# MCU.net
KiCad netlist of a schematic drawn in Altium Designer
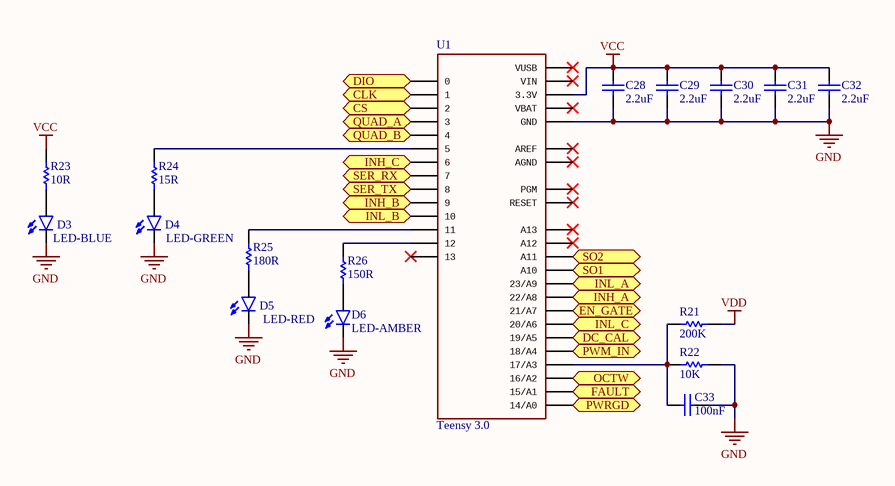
[diagram p0: MCU.SchDoc]

(export (version "E")
  (design (tool "Eeschema 10.0.6"))
  (components
    (comp (ref "C28")
      (value "2.2uF")
      (footprint "CAPC0603(1608)55_N")
      (description "CAP 2.2uF 16V Â±10% 0603 (1608 Metric) Thickness 0.55mm SMD")
      (fields (field (name "TOLERANCE") "Â±10%"))
      (libsource (lib "Altium Content Vault") (part "CMP-1035-02762-1"))
    )
    (comp (ref "C29")
      (value "2.2uF")
      (footprint "CAPC0603(1608)55_N")
      (description "CAP 2.2uF 16V Â±10% 0603 (1608 Metric) Thickness 0.55mm SMD")
      (fields (field (name "TOLERANCE") "Â±10%"))
      (libsource (lib "Altium Content Vault") (part "CMP-1035-02762-1"))
    )
    (comp (ref "C30")
      (value "2.2uF")
      (footprint "CAPC0603(1608)55_N")
      (description "CAP 2.2uF 16V Â±10% 0603 (1608 Metric) Thickness 0.55mm SMD")
      (fields (field (name "TOLERANCE") "Â±10%"))
      (libsource (lib "Altium Content Vault") (part "CMP-1035-02762-1"))
    )
    (comp (ref "C31")
      (value "2.2uF")
      (footprint "CAPC0603(1608)55_N")
      (description "CAP 2.2uF 16V Â±10% 0603 (1608 Metric) Thickness 0.55mm SMD")
      (fields (field (name "TOLERANCE") "Â±10%"))
      (libsource (lib "Altium Content Vault") (part "CMP-1035-02762-1"))
    )
    (comp (ref "C32")
      (value "2.2uF")
      (footprint "CAPC0603(1608)55_N")
      (description "CAP 2.2uF 16V Â±10% 0603 (1608 Metric) Thickness 0.55mm SMD")
      (fields (field (name "TOLERANCE") "Â±10%"))
      (libsource (lib "Altium Content Vault") (part "CMP-1035-02762-1"))
    )
    (comp (ref "C33")
      (value "100nF")
      (footprint "CAPC0603(1608)100_L")
      (description "CAP 100nF 50V Â±5% 0603 (1608 Metric) Thickness 1mm SMD")
      (fields (field (name "TOLERANCE") "Â±5%"))
      (libsource (lib "Altium Content Vault") (part "CAP"))
    )
    (comp (ref "D3")
      (value "LED-BLUE")
      (footprint "LED-1206")
      (libsource (lib "Components") (part "LED-BLUE1206"))
    )
    (comp (ref "D4")
      (value "LED-GREEN")
      (footprint "LED-1206")
      (libsource (lib "Components") (part "LED-GREEN1206"))
    )
    (comp (ref "D5")
      (value "LED-RED")
      (footprint "LED-1206")
      (libsource (lib "Components") (part "LED-RED1206"))
    )
    (comp (ref "D6")
      (value "LED-AMBER")
      (footprint "LED-1206")
      (libsource (lib "Components") (part "LED-AMBER1206"))
    )
    (comp (ref "R21")
      (value "200K")
      (footprint "RESC0603(1608)_L")
      (description "200K 0.1W 5% 0603 (1608 Metric)  SMD")
      (fields (field (name "POWER") "0.1 W") (field (name "TOLERANCE") "5 %"))
      (libsource (lib "Altium Content Vault") (part "RES"))
    )
    (comp (ref "R22")
      (value "10K")
      (footprint "RESC0603(1608)_M")
      (description "10K 0.1W 5% 0603 (1608 Metric)  SMD")
      (fields (field (name "TOLERANCE") "5 %") (field (name "POWER") "0.1 W"))
      (libsource (lib "Altium Content Vault") (part "RES"))
    )
    (comp (ref "R23")
      (value "10R")
      (footprint "RESC0603(1608)_N")
      (description "10R 0.1W 5% 0603 (1608 Metric)  SMD")
      (fields (field (name "TOLERANCE") "5 %") (field (name "POWER") "0.1 W"))
      (libsource (lib "Altium Content Vault") (part "CMP-1012-00026-1"))
    )
    (comp (ref "R24")
      (value "15R")
      (footprint "RESC0603(1608)_N")
      (description "15R 0.1W 5% 0603 (1608 Metric)  SMD")
      (fields (field (name "TOLERANCE") "5 %") (field (name "POWER") "0.1 W"))
      (libsource (lib "Altium Content Vault") (part "CMP-1012-00030-1"))
    )
    (comp (ref "R25")
      (value "180R")
      (footprint "RESC0603(1608)_N")
      (description "180R 0.1W 5% 0603 (1608 Metric)  SMD")
      (fields (field (name "POWER") "0.1 W") (field (name "TOLERANCE") "5 %"))
      (libsource (lib "Altium Content Vault") (part "CMP-1012-00056-1"))
    )
    (comp (ref "R26")
      (value "150R")
      (footprint "RESC0603(1608)_N")
      (description "150R 0.1W 5% 0603 (1608 Metric)  SMD")
      (fields (field (name "POWER") "0.1 W") (field (name "TOLERANCE") "5 %"))
      (libsource (lib "Altium Content Vault") (part "CMP-1012-00054-1"))
    )
    (comp (ref "U1")
      (value "Teensy 3.0")
      (footprint "TEENSY_3.0_ALLANALOG")
      (libsource (lib "Teensy3.0") (part "TEENSY_3.0_ALLANALOGPINS"))
    )
  )
  (nets
    (net (code "1") (name "/CLK") (class "Default")
      (node (ref "U1") (pin "1") (pinfunction "1_1") (pintype "passive"))
    )
    (net (code "2") (name "/CS") (class "Default")
      (node (ref "U1") (pin "2") (pinfunction "2_2") (pintype "passive"))
    )
    (net (code "3") (name "/DC_CAL") (class "Default")
      (node (ref "U1") (pin "19/A5") (pinfunction "19/A5_19/A5") (pintype "passive"))
    )
    (net (code "4") (name "/DIO") (class "Default")
      (node (ref "U1") (pin "0") (pinfunction "0_0") (pintype "passive"))
    )
    (net (code "5") (name "/EN_GATE") (class "Default")
      (node (ref "U1") (pin "21/A7") (pinfunction "21/A7_21/A7") (pintype "passive"))
    )
    (net (code "6") (name "/FAULT") (class "Default")
      (node (ref "U1") (pin "15/A1") (pinfunction "15/A1_15/A1") (pintype "passive"))
    )
    (net (code "7") (name "/INH_A") (class "Default")
      (node (ref "U1") (pin "22/A8") (pinfunction "22/A8_22/A8") (pintype "passive"))
    )
    (net (code "8") (name "/INH_B") (class "Default")
      (node (ref "U1") (pin "9") (pinfunction "9_9") (pintype "passive"))
    )
    (net (code "9") (name "/INH_C") (class "Default")
      (node (ref "U1") (pin "6") (pinfunction "6_6") (pintype "passive"))
    )
    (net (code "10") (name "/INL_A") (class "Default")
      (node (ref "U1") (pin "23/A9") (pinfunction "23/A9_23/A9") (pintype "passive"))
    )
    (net (code "11") (name "/INL_B") (class "Default")
      (node (ref "U1") (pin "10") (pinfunction "10_10") (pintype "passive"))
    )
    (net (code "12") (name "/INL_C") (class "Default")
      (node (ref "U1") (pin "20/A6") (pinfunction "20/A6_20/A6") (pintype "passive"))
    )
    (net (code "13") (name "/OCTW") (class "Default")
      (node (ref "U1") (pin "16/A2") (pinfunction "16/A2_16/A2") (pintype "passive"))
    )
    (net (code "14") (name "/PWM_IN") (class "Default")
      (node (ref "U1") (pin "18/A4") (pinfunction "18/A4_18/A4") (pintype "passive"))
    )
    (net (code "15") (name "/PWRGD") (class "Default")
      (node (ref "U1") (pin "14/A0") (pinfunction "14/A0_14/A0") (pintype "passive"))
    )
    (net (code "16") (name "/QUAD_A") (class "Default")
      (node (ref "U1") (pin "3") (pinfunction "3_3") (pintype "passive"))
    )
    (net (code "17") (name "/QUAD_B") (class "Default")
      (node (ref "U1") (pin "4") (pinfunction "4_4") (pintype "passive"))
    )
    (net (code "18") (name "/SER_RX") (class "Default")
      (node (ref "U1") (pin "7") (pinfunction "7_7") (pintype "passive"))
    )
    (net (code "19") (name "/SER_TX") (class "Default")
      (node (ref "U1") (pin "8") (pinfunction "8_8") (pintype "passive"))
    )
    (net (code "20") (name "/SO1") (class "Default")
      (node (ref "U1") (pin "A10") (pinfunction "A10_A10") (pintype "passive"))
    )
    (net (code "21") (name "/SO2") (class "Default")
      (node (ref "U1") (pin "A11") (pinfunction "A11_A11") (pintype "passive"))
    )
    (net (code "22") (name "GND") (class "Default")
      (node (ref "C28") (pin "1") (pinfunction "1_1") (pintype "passive"))
      (node (ref "C29") (pin "1") (pinfunction "1_1") (pintype "passive"))
      (node (ref "C30") (pin "1") (pinfunction "1_1") (pintype "passive"))
      (node (ref "C31") (pin "1") (pinfunction "1_1") (pintype "passive"))
      (node (ref "C32") (pin "1") (pinfunction "1_1") (pintype "passive"))
      (node (ref "C33") (pin "2") (pinfunction "2_2") (pintype "passive"))
      (node (ref "D3") (pin "C") (pinfunction "C_C") (pintype "passive"))
      (node (ref "D4") (pin "C") (pinfunction "C_C") (pintype "passive"))
      (node (ref "D5") (pin "C") (pinfunction "C_C") (pintype "passive"))
      (node (ref "D6") (pin "C") (pinfunction "C_C") (pintype "passive"))
      (node (ref "R22") (pin "2") (pinfunction "2_2") (pintype "passive"))
      (node (ref "U1") (pin "GND_GND1_GND2") (pinfunction "GND_GND_GND1_GND2") (pintype "power_in"))
    )
    (net (code "23") (name "Net-(C33-Pad1)") (class "Default")
      (node (ref "C33") (pin "1") (pinfunction "1_1") (pintype "passive"))
      (node (ref "R21") (pin "1") (pinfunction "1_1") (pintype "passive"))
      (node (ref "R22") (pin "1") (pinfunction "1_1") (pintype "passive"))
      (node (ref "U1") (pin "17/A3") (pinfunction "17/A3_17/A3") (pintype "passive"))
    )
    (net (code "24") (name "Net-(D3-PadA)") (class "Default")
      (node (ref "D3") (pin "A") (pinfunction "A_A") (pintype "passive"))
      (node (ref "R23") (pin "1") (pinfunction "1_1") (pintype "passive"))
    )
    (net (code "25") (name "Net-(D4-PadA)") (class "Default")
      (node (ref "D4") (pin "A") (pinfunction "A_A") (pintype "passive"))
      (node (ref "R24") (pin "1") (pinfunction "1_1") (pintype "passive"))
    )
    (net (code "26") (name "Net-(D5-PadA)") (class "Default")
      (node (ref "D5") (pin "A") (pinfunction "A_A") (pintype "passive"))
      (node (ref "R25") (pin "1") (pinfunction "1_1") (pintype "passive"))
    )
    (net (code "27") (name "Net-(D6-PadA)") (class "Default")
      (node (ref "D6") (pin "A") (pinfunction "A_A") (pintype "passive"))
      (node (ref "R26") (pin "1") (pinfunction "1_1") (pintype "passive"))
    )
    (net (code "28") (name "Net-(R24-Pad2)") (class "Default")
      (node (ref "R24") (pin "2") (pinfunction "2_2") (pintype "passive"))
      (node (ref "U1") (pin "5") (pinfunction "5_5") (pintype "passive"))
    )
    (net (code "29") (name "Net-(R25-Pad2)") (class "Default")
      (node (ref "R25") (pin "2") (pinfunction "2_2") (pintype "passive"))
      (node (ref "U1") (pin "11") (pinfunction "11_11") (pintype "passive"))
    )
    (net (code "30") (name "Net-(R26-Pad2)") (class "Default")
      (node (ref "R26") (pin "2") (pinfunction "2_2") (pintype "passive"))
      (node (ref "U1") (pin "12") (pinfunction "12_12") (pintype "passive"))
    )
    (net (code "31") (name "VCC") (class "Default")
      (node (ref "C28") (pin "2") (pinfunction "2_2") (pintype "passive"))
      (node (ref "C29") (pin "2") (pinfunction "2_2") (pintype "passive"))
      (node (ref "C30") (pin "2") (pinfunction "2_2") (pintype "passive"))
      (node (ref "C31") (pin "2") (pinfunction "2_2") (pintype "passive"))
      (node (ref "C32") (pin "2") (pinfunction "2_2") (pintype "passive"))
      (node (ref "R23") (pin "2") (pinfunction "2_2") (pintype "passive"))
      (node (ref "U1") (pin "3.3V_3.3V1_3.3V2") (pinfunction "3.3V_3.3V_3.3V1_3.3V2") (pintype "power_in"))
    )
    (net (code "32") (name "VDD") (class "Default")
      (node (ref "R21") (pin "2") (pinfunction "2_2") (pintype "passive"))
    )
    (net (code "33") (name "unconnected-(U1-Pad13)") (class "Default")
      (node (ref "U1") (pin "13") (pinfunction "13_13") (pintype "passive+no_connect"))
    )
    (net (code "34") (name "unconnected-(U1-PadA12)") (class "Default")
      (node (ref "U1") (pin "A12") (pinfunction "A12_A12") (pintype "passive+no_connect"))
    )
    (net (code "35") (name "unconnected-(U1-PadA13)") (class "Default")
      (node (ref "U1") (pin "A13") (pinfunction "A13_A13") (pintype "passive+no_connect"))
    )
    (net (code "36") (name "unconnected-(U1-PadAGND)") (class "Default")
      (node (ref "U1") (pin "AGND") (pinfunction "AGND_AGND") (pintype "power_in+no_connect"))
    )
    (net (code "37") (name "unconnected-(U1-PadAREF)") (class "Default")
      (node (ref "U1") (pin "AREF") (pinfunction "AREF_AREF") (pintype "power_in+no_connect"))
    )
    (net (code "38") (name "unconnected-(U1-PadPGM)") (class "Default")
      (node (ref "U1") (pin "PGM") (pinfunction "PGM_PGM") (pintype "power_in+no_connect"))
    )
    (net (code "39") (name "unconnected-(U1-PadVBAT)") (class "Default")
      (node (ref "U1") (pin "VBAT") (pinfunction "VBAT_VBAT") (pintype "power_in+no_connect"))
    )
    (net (code "40") (name "unconnected-(U1-PadVIN)") (class "Default")
      (node (ref "U1") (pin "VIN") (pinfunction "VIN_VIN") (pintype "power_in+no_connect"))
    )
    (net (code "41") (name "unconnected-(U1-PadVUSB)") (class "Default")
      (node (ref "U1") (pin "VUSB") (pinfunction "VUSB_VUSB") (pintype "power_in+no_connect"))
    )
    (net (code "42") (name "unconnected-(U1-RESET-PadRST)") (class "Default")
      (node (ref "U1") (pin "RST") (pinfunction "RESET_RST") (pintype "power_in+no_connect"))
    )
  )
)
